# 08_-_AUDIO.net
KiCad netlist of a schematic drawn in Altium Designer
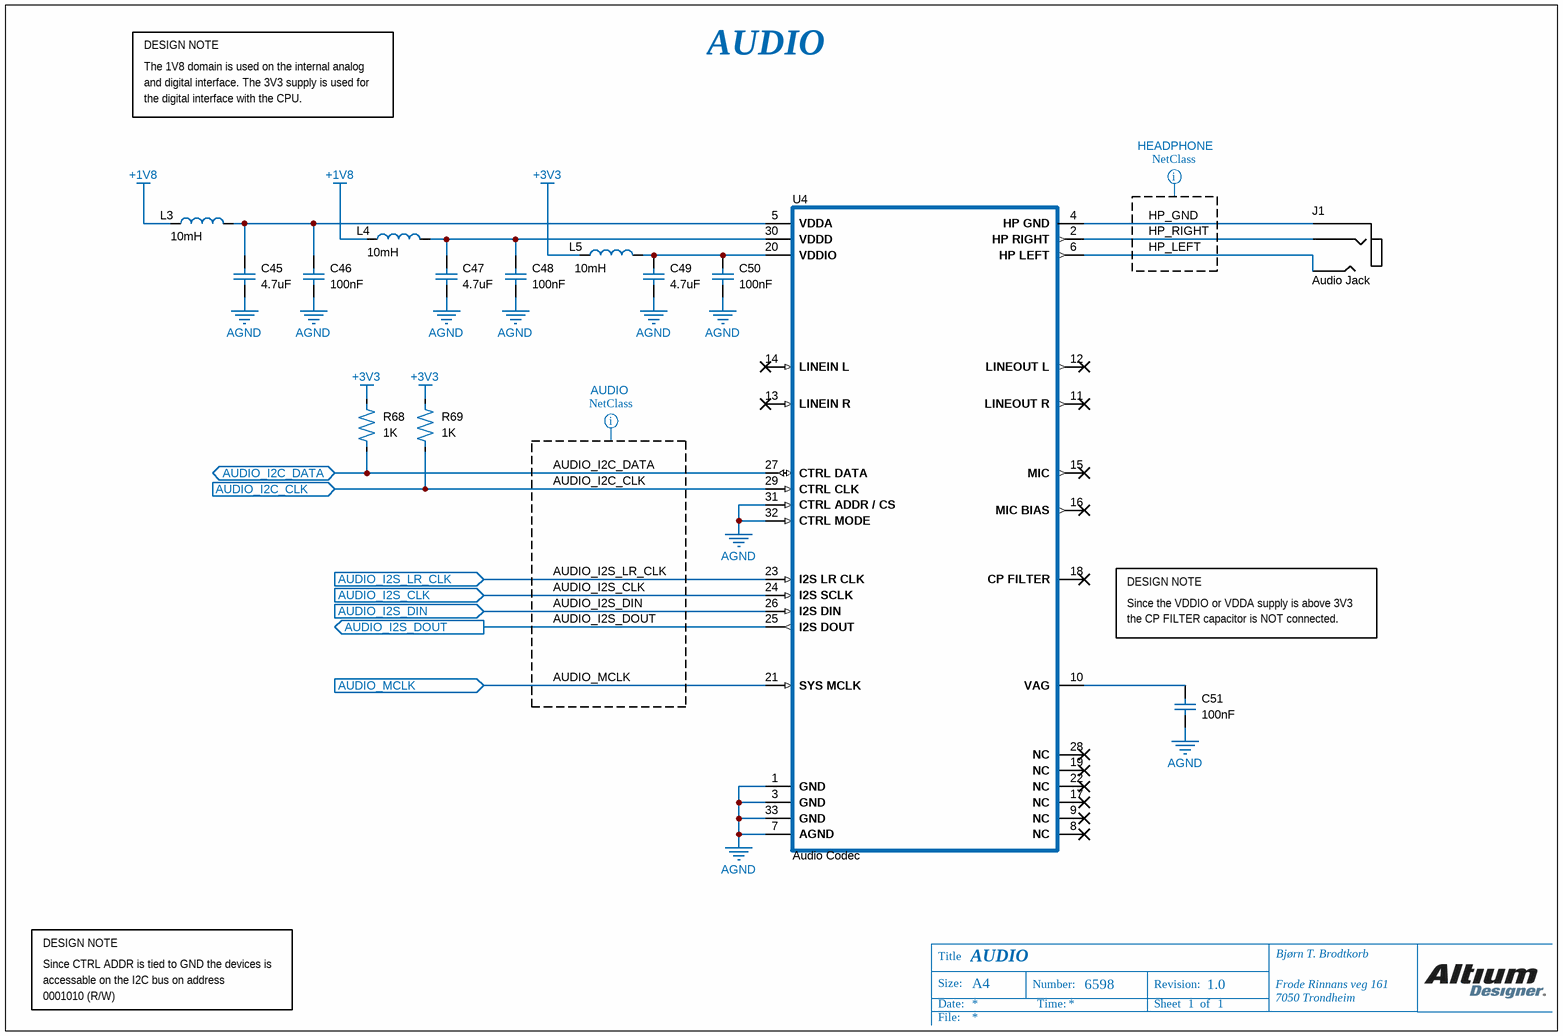
[diagram p0: [08] - AUDIO.SchDoc]

(export (version "E")
  (design (tool "Eeschema 10.0.6"))
  (components
    (comp (ref "C45")
      (value "4.7uF")
      (footprint "C0603")
      (description "C0603")
      (fields (field (name "Comment") "02016D104KAT2A"))
      (libsource (lib "Passive components") (part "02016D104KAT2A"))
    )
    (comp (ref "C46")
      (value "100nF")
      (footprint "C0402")
      (description "C0402")
      (fields (field (name "Comment") "04023C103KAT2A"))
      (libsource (lib "Passive components") (part "04023C103KAT2A"))
    )
    (comp (ref "C47")
      (value "4.7uF")
      (footprint "C0603")
      (description "C0603")
      (fields (field (name "Comment") "02016D104KAT2A"))
      (libsource (lib "Passive components") (part "02016D104KAT2A"))
    )
    (comp (ref "C48")
      (value "100nF")
      (footprint "C0402")
      (description "C0402")
      (fields (field (name "Comment") "04023C103KAT2A"))
      (libsource (lib "Passive components") (part "04023C103KAT2A"))
    )
    (comp (ref "C49")
      (value "4.7uF")
      (footprint "C0603")
      (description "C0603")
      (fields (field (name "Comment") "02016D104KAT2A"))
      (libsource (lib "Passive components") (part "02016D104KAT2A"))
    )
    (comp (ref "C50")
      (value "100nF")
      (footprint "C0402")
      (description "C0402")
      (fields (field (name "Comment") "04023C103KAT2A"))
      (libsource (lib "Passive components") (part "04023C103KAT2A"))
    )
    (comp (ref "C51")
      (value "100nF")
      (footprint "C0402")
      (description "C0402")
      (fields (field (name "Comment") "04023C103KAT2A"))
      (libsource (lib "Passive components") (part "04023C103KAT2A"))
    )
    (comp (ref "J1")
      (value "Audio Jack")
      (footprint "Audio jack barrel 3 contacts")
      (description "Audio jack barrel 3 contacts")
      (libsource (lib "Connectors") (part "SJ-3524-SMT-TR"))
    )
    (comp (ref "L3")
      (value "10mH")
      (footprint "Inductor 0603")
      (description "Inductor 0603")
      (fields (field (name "Comment") "MLZ1608A2R2WT"))
      (libsource (lib "Passive components") (part "MLZ1608A2R2WT"))
    )
    (comp (ref "L4")
      (value "10mH")
      (footprint "Inductor 0603")
      (description "Inductor 0603")
      (fields (field (name "Comment") "MLZ1608A2R2WT"))
      (libsource (lib "Passive components") (part "MLZ1608A2R2WT"))
    )
    (comp (ref "L5")
      (value "10mH")
      (footprint "Inductor 0603")
      (description "Inductor 0603")
      (fields (field (name "Comment") "MLZ1608A2R2WT"))
      (libsource (lib "Passive components") (part "MLZ1608A2R2WT"))
    )
    (comp (ref "R68")
      (value "1K")
      (footprint "R0402")
      (description "R0402")
      (fields (field (name "Comment") "CRCW04020000Z0ED"))
      (libsource (lib "Passive components") (part "CRCW04020000Z0ED"))
    )
    (comp (ref "R69")
      (value "1K")
      (footprint "R0402")
      (description "R0402")
      (fields (field (name "Comment") "CRCW04020000Z0ED"))
      (libsource (lib "Passive components") (part "CRCW04020000Z0ED"))
    )
    (comp (ref "U4")
      (value "Audio Codec")
      (footprint "SGTL5000XNAA3")
      (description "Audio codec w/ headophone amp")
      (libsource (lib "IC") (part "SGTL5000XNAA3"))
    )
  )
  (nets
    (net (code "1") (name "+1V8") (class "Default")
      (node (ref "L3") (pin "1") (pinfunction "1_1") (pintype "passive"))
      (node (ref "L4") (pin "1") (pinfunction "1_1") (pintype "passive"))
    )
    (net (code "2") (name "+3V3") (class "Default")
      (node (ref "L5") (pin "1") (pinfunction "1_1") (pintype "passive"))
      (node (ref "R68") (pin "2") (pinfunction "3_2") (pintype "passive"))
      (node (ref "R69") (pin "2") (pinfunction "3_2") (pintype "passive"))
    )
    (net (code "3") (name "/AUDIO_I2C_CLK") (class "Default")
      (node (ref "R69") (pin "1") (pinfunction "1_1") (pintype "passive"))
      (node (ref "U4") (pin "29") (pinfunction "CTRL_CLK_29") (pintype "input"))
    )
    (net (code "4") (name "/AUDIO_I2C_DATA") (class "Default")
      (node (ref "R68") (pin "1") (pinfunction "1_1") (pintype "passive"))
      (node (ref "U4") (pin "27") (pinfunction "CTRL_DATA_27") (pintype "bidirectional"))
    )
    (net (code "5") (name "/AUDIO_I2S_CLK") (class "Default")
      (node (ref "U4") (pin "24") (pinfunction "I2S_SCLK_24") (pintype "input"))
    )
    (net (code "6") (name "/AUDIO_I2S_DIN") (class "Default")
      (node (ref "U4") (pin "26") (pinfunction "I2S_DIN_26") (pintype "input"))
    )
    (net (code "7") (name "/AUDIO_I2S_DOUT") (class "Default")
      (node (ref "U4") (pin "25") (pinfunction "I2S_DOUT_25") (pintype "output"))
    )
    (net (code "8") (name "/AUDIO_I2S_LR_CLK") (class "Default")
      (node (ref "U4") (pin "23") (pinfunction "I2S_LR_CLK_23") (pintype "input"))
    )
    (net (code "9") (name "/AUDIO_MCLK") (class "Default")
      (node (ref "U4") (pin "21") (pinfunction "SYS_MCLK_21") (pintype "input"))
    )
    (net (code "10") (name "/HP_GND") (class "Default")
      (node (ref "J1") (pin "1") (pinfunction "1_1") (pintype "passive"))
      (node (ref "U4") (pin "4") (pinfunction "HP_GND_4") (pintype "power_in"))
    )
    (net (code "11") (name "/HP_LEFT") (class "Default")
      (node (ref "J1") (pin "2") (pinfunction "2_2") (pintype "passive"))
      (node (ref "U4") (pin "6") (pinfunction "HP_LEFT_6") (pintype "output"))
    )
    (net (code "12") (name "/HP_RIGHT") (class "Default")
      (node (ref "J1") (pin "3") (pinfunction "3_3") (pintype "passive"))
      (node (ref "U4") (pin "2") (pinfunction "HP_RIGHT_2") (pintype "output"))
    )
    (net (code "13") (name "AGND") (class "Default")
      (node (ref "C45") (pin "2") (pinfunction "2_2") (pintype "passive"))
      (node (ref "C46") (pin "2") (pinfunction "2_2") (pintype "passive"))
      (node (ref "C47") (pin "2") (pinfunction "2_2") (pintype "passive"))
      (node (ref "C48") (pin "2") (pinfunction "2_2") (pintype "passive"))
      (node (ref "C49") (pin "2") (pinfunction "2_2") (pintype "passive"))
      (node (ref "C50") (pin "2") (pinfunction "2_2") (pintype "passive"))
      (node (ref "C51") (pin "2") (pinfunction "2_2") (pintype "passive"))
      (node (ref "U4") (pin "1") (pinfunction "GND_1") (pintype "power_in"))
      (node (ref "U4") (pin "3") (pinfunction "GND_3") (pintype "power_in"))
      (node (ref "U4") (pin "31") (pinfunction "CTRL_ADDR_/_CS_31") (pintype "input"))
      (node (ref "U4") (pin "32") (pinfunction "CTRL_MODE_32") (pintype "input"))
      (node (ref "U4") (pin "33") (pinfunction "GND_33") (pintype "power_in"))
      (node (ref "U4") (pin "7") (pinfunction "AGND_7") (pintype "power_in"))
    )
    (net (code "14") (name "Net-(U4-VAG)") (class "Default")
      (node (ref "C51") (pin "1") (pinfunction "1_1") (pintype "passive"))
      (node (ref "U4") (pin "10") (pinfunction "VAG_10") (pintype "passive"))
    )
    (net (code "15") (name "Net-(U4-VDDA)") (class "Default")
      (node (ref "C45") (pin "1") (pinfunction "1_1") (pintype "passive"))
      (node (ref "C46") (pin "1") (pinfunction "1_1") (pintype "passive"))
      (node (ref "L3") (pin "2") (pinfunction "2_2") (pintype "passive"))
      (node (ref "U4") (pin "5") (pinfunction "VDDA_5") (pintype "power_in"))
    )
    (net (code "16") (name "Net-(U4-VDDD)") (class "Default")
      (node (ref "C47") (pin "1") (pinfunction "1_1") (pintype "passive"))
      (node (ref "C48") (pin "1") (pinfunction "1_1") (pintype "passive"))
      (node (ref "L4") (pin "2") (pinfunction "2_2") (pintype "passive"))
      (node (ref "U4") (pin "30") (pinfunction "VDDD_30") (pintype "power_in"))
    )
    (net (code "17") (name "Net-(U4-VDDIO)") (class "Default")
      (node (ref "C49") (pin "1") (pinfunction "1_1") (pintype "passive"))
      (node (ref "C50") (pin "1") (pinfunction "1_1") (pintype "passive"))
      (node (ref "L5") (pin "2") (pinfunction "2_2") (pintype "passive"))
      (node (ref "U4") (pin "20") (pinfunction "VDDIO_20") (pintype "power_in"))
    )
    (net (code "18") (name "unconnected-(U4-CP_FILTER-Pad18)") (class "Default")
      (node (ref "U4") (pin "18") (pinfunction "CP_FILTER_18") (pintype "passive+no_connect"))
    )
    (net (code "19") (name "unconnected-(U4-LINEIN_L-Pad14)") (class "Default")
      (node (ref "U4") (pin "14") (pinfunction "LINEIN_L_14") (pintype "input+no_connect"))
    )
    (net (code "20") (name "unconnected-(U4-LINEIN_R-Pad13)") (class "Default")
      (node (ref "U4") (pin "13") (pinfunction "LINEIN_R_13") (pintype "input+no_connect"))
    )
    (net (code "21") (name "unconnected-(U4-LINEOUT_L-Pad12)") (class "Default")
      (node (ref "U4") (pin "12") (pinfunction "LINEOUT_L_12") (pintype "output+no_connect"))
    )
    (net (code "22") (name "unconnected-(U4-LINEOUT_R-Pad11)") (class "Default")
      (node (ref "U4") (pin "11") (pinfunction "LINEOUT_R_11") (pintype "output+no_connect"))
    )
    (net (code "23") (name "unconnected-(U4-MIC-Pad15)") (class "Default")
      (node (ref "U4") (pin "15") (pinfunction "MIC_15") (pintype "output+no_connect"))
    )
    (net (code "24") (name "unconnected-(U4-MIC_BIAS-Pad16)") (class "Default")
      (node (ref "U4") (pin "16") (pinfunction "MIC_BIAS_16") (pintype "output+no_connect"))
    )
    (net (code "25") (name "unconnected-(U4-NC-Pad8)") (class "Default")
      (node (ref "U4") (pin "8") (pinfunction "NC_8") (pintype "passive+no_connect"))
    )
    (net (code "26") (name "unconnected-(U4-NC-Pad9)") (class "Default")
      (node (ref "U4") (pin "9") (pinfunction "NC_9") (pintype "passive+no_connect"))
    )
    (net (code "27") (name "unconnected-(U4-NC-Pad17)") (class "Default")
      (node (ref "U4") (pin "17") (pinfunction "NC_17") (pintype "passive+no_connect"))
    )
    (net (code "28") (name "unconnected-(U4-NC-Pad19)") (class "Default")
      (node (ref "U4") (pin "19") (pinfunction "NC_19") (pintype "passive+no_connect"))
    )
    (net (code "29") (name "unconnected-(U4-NC-Pad22)") (class "Default")
      (node (ref "U4") (pin "22") (pinfunction "NC_22") (pintype "passive+no_connect"))
    )
    (net (code "30") (name "unconnected-(U4-NC-Pad28)") (class "Default")
      (node (ref "U4") (pin "28") (pinfunction "NC_28") (pintype "passive+no_connect"))
    )
  )
)
